# Aux_Lights_Daughter_REV2_1.net
KiCad netlist of a schematic drawn in Altium Designer
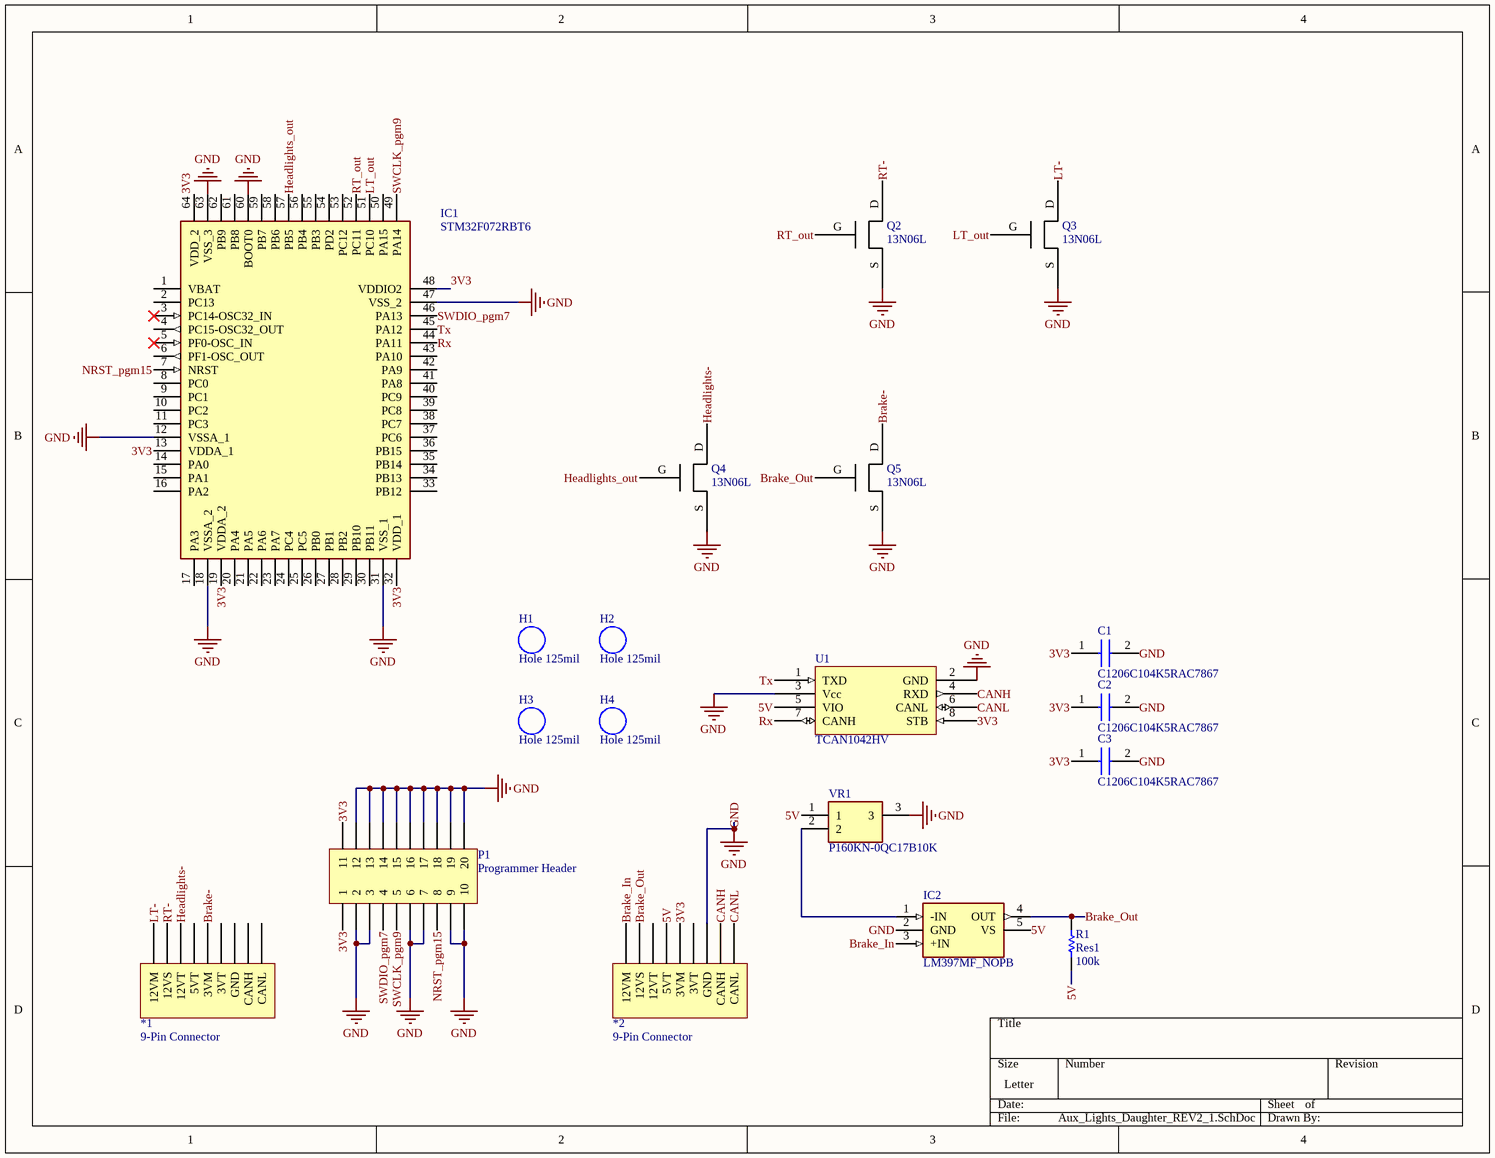
[diagram p0: Aux_Lights_Daughter_REV2_1.SchDoc]

(export (version "E")
  (design (tool "Eeschema 10.0.6"))
  (components
    (comp (ref "*1")
      (value "9-Pin Connector")
      (footprint "9-Pin")
      (libsource (lib "SolarGators") (part "9-Pin Connector"))
    )
    (comp (ref "*2")
      (value "9-Pin Connector")
      (footprint "9-Pin")
      (libsource (lib "SolarGators") (part "9-Pin Connector"))
    )
    (comp (ref "C1")
      (value "C1206C104K5RAC7867")
      (footprint "SamacSys:CAPC3216X110N")
      (description "Capacitor")
      (fields (field (name "MOUSER2 PART NUMBER") "80-C1206104K5RAC7867"))
      (libsource (lib "*") (part "C1206C104K5RAC7867"))
    )
    (comp (ref "C2")
      (value "C1206C104K5RAC7867")
      (footprint "SamacSys:CAPC3216X110N")
      (description "Capacitor")
      (fields (field (name "MOUSER2 PART NUMBER") "80-C1206104K5RAC7867"))
      (libsource (lib "*") (part "C1206C104K5RAC7867"))
    )
    (comp (ref "C3")
      (value "C1206C104K5RAC7867")
      (footprint "SamacSys:CAPC3216X110N")
      (description "Capacitor")
      (fields (field (name "MOUSER2 PART NUMBER") "80-C1206104K5RAC7867"))
      (libsource (lib "*") (part "C1206C104K5RAC7867"))
    )
    (comp (ref "H1")
      (value "Hole 125mil")
      (footprint "Hole 125mil")
      (libsource (lib "ECE LIB new") (part "Hole 125mil"))
    )
    (comp (ref "H2")
      (value "Hole 125mil")
      (footprint "Hole 125mil")
      (libsource (lib "ECE LIB new") (part "Hole 125mil"))
    )
    (comp (ref "H3")
      (value "Hole 125mil")
      (footprint "Hole 125mil")
      (libsource (lib "ECE LIB new") (part "Hole 125mil"))
    )
    (comp (ref "H4")
      (value "Hole 125mil")
      (footprint "Hole 125mil")
      (libsource (lib "ECE LIB new") (part "Hole 125mil"))
    )
    (comp (ref "IC1")
      (value "STM32F072RBT6")
      (footprint "QFP50P1200X1200X160-64N")
      (description "Integrated Circuit")
      (fields (field (name "MOUSER PART NUMBER") "511-STM32F072RBT6"))
      (libsource (lib "solargatorsproject") (part "STM32F072RBT6"))
    )
    (comp (ref "IC2")
      (value "LM397MF_NOPB")
      (footprint "SamacSys:SOT95P280X145-5N")
      (description "Integrated Circuit")
      (fields
        (field (name "MOUSER PART NUMBER") "926-LM397MF/NOPB")
        (field (name "MANUFACTURER_PART_NUMBER") "LM397MF/NOPB")
      )
      (libsource (lib "*") (part "LM397MF_NOPB"))
    )
    (comp (ref "P1")
      (value "Programmer Header")
      (footprint "HDR2X10_CEN")
      (description "Header, 10-Pin, Dual row")
      (fields (field (name "PUBLISHER") "Altium Limited"))
      (libsource (lib "Miscellaneous Connectors") (part "Header 10X2A"))
    )
    (comp (ref "Q2") (value "13N06L") (footprint "13N06L") (libsource (lib "SolarGators") (part "13N06L")))
    (comp (ref "Q3") (value "13N06L") (footprint "13N06L") (libsource (lib "SolarGators") (part "13N06L")))
    (comp (ref "Q4") (value "13N06L") (footprint "13N06L") (libsource (lib "SolarGators") (part "13N06L")))
    (comp (ref "Q5") (value "13N06L") (footprint "13N06L") (libsource (lib "SolarGators") (part "13N06L")))
    (comp (ref "R1")
      (value "Res1")
      (footprint "AXIAL-0.3")
      (description "Resistor")
      (fields (field (name "ALTIUM_VALUE") "100k") (field (name "PUBLISHER") "Altium Limited"))
      (libsource (lib "Miscellaneous Devices") (part "Res1"))
    )
    (comp (ref "U1")
      (value "TCAN1042HV")
      (footprint "CANIC")
      (description "TCAN1042Fault ProtectedCAN Transceiverwith CAN FD")
      (libsource (lib "Schlib1") (part "TCAN1042HV"))
    )
    (comp (ref "VR1")
      (value "P160KN-0QC17B10K")
      (footprint "POT inline wide")
      (description "Variable Resistor")
      (fields (field (name "MOUSER PART NUMBER") "858-P160KN-OQC17B10K"))
      (libsource (lib "*") (part "P160KN-0QC17B10K"))
    )
  )
  (nets
    (net (code "1") (name "/3V3") (class "Default")
      (node (ref "*2") (pin "5") (pinfunction "3VM_5") (pintype "passive"))
      (node (ref "C1") (pin "1") (pinfunction "1_1") (pintype "passive"))
      (node (ref "C2") (pin "1") (pinfunction "1_1") (pintype "passive"))
      (node (ref "C3") (pin "1") (pinfunction "1_1") (pintype "passive"))
      (node (ref "IC1") (pin "13") (pinfunction "VDDA_1_13") (pintype "power_in"))
      (node (ref "IC1") (pin "19") (pinfunction "VDDA_2_19") (pintype "power_in"))
      (node (ref "IC1") (pin "32") (pinfunction "VDD_1_32") (pintype "power_in"))
      (node (ref "IC1") (pin "48") (pinfunction "VDDIO2_48") (pintype "power_in"))
      (node (ref "IC1") (pin "64") (pinfunction "VDD_2_64") (pintype "power_in"))
      (node (ref "P1") (pin "1") (pinfunction "1_1") (pintype "passive"))
      (node (ref "P1") (pin "11") (pinfunction "11_11") (pintype "passive"))
      (node (ref "U1") (pin "8") (pinfunction "STB_8") (pintype "input"))
    )
    (net (code "2") (name "/5V") (class "Default")
      (node (ref "*2") (pin "4") (pinfunction "5VT_4") (pintype "passive"))
      (node (ref "IC2") (pin "5") (pinfunction "VS_5") (pintype "passive"))
      (node (ref "R1") (pin "1") (pinfunction "1_1") (pintype "passive"))
      (node (ref "U1") (pin "5") (pinfunction "VIO_5") (pintype "power_in"))
      (node (ref "VR1") (pin "1") (pinfunction "1_1") (pintype "passive"))
    )
    (net (code "3") (name "/Brake-") (class "Default")
      (node (ref "*1") (pin "5") (pinfunction "3VM_5") (pintype "passive"))
      (node (ref "Q5") (pin "D") (pinfunction "14_D") (pintype "passive"))
    )
    (net (code "4") (name "/Brake_In") (class "Default")
      (node (ref "*2") (pin "1") (pinfunction "12VM_1") (pintype "passive"))
      (node (ref "IC2") (pin "3") (pinfunction "+IN_3") (pintype "input"))
    )
    (net (code "5") (name "/Brake_Out") (class "Default")
      (node (ref "*2") (pin "2") (pinfunction "12VS_2") (pintype "passive"))
      (node (ref "IC2") (pin "4") (pinfunction "OUT_4") (pintype "output"))
      (node (ref "Q5") (pin "G") (pinfunction "13_G") (pintype "passive"))
      (node (ref "R1") (pin "2") (pinfunction "2_2") (pintype "passive"))
    )
    (net (code "6") (name "/CANH") (class "Default")
      (node (ref "*2") (pin "8") (pinfunction "CANH_8") (pintype "passive"))
      (node (ref "U1") (pin "4") (pinfunction "RXD_4") (pintype "output"))
    )
    (net (code "7") (name "/CANL") (class "Default")
      (node (ref "*2") (pin "9") (pinfunction "CANL_9") (pintype "passive"))
      (node (ref "U1") (pin "6") (pinfunction "CANL_6") (pintype "bidirectional"))
    )
    (net (code "8") (name "/Headlights-") (class "Default")
      (node (ref "*1") (pin "3") (pinfunction "12VT_3") (pintype "passive"))
      (node (ref "Q4") (pin "D") (pinfunction "14_D") (pintype "passive"))
    )
    (net (code "9") (name "/Headlights_out") (class "Default")
      (node (ref "IC1") (pin "57") (pinfunction "PB5_57") (pintype "passive"))
      (node (ref "Q4") (pin "G") (pinfunction "13_G") (pintype "passive"))
    )
    (net (code "10") (name "/LT-") (class "Default")
      (node (ref "*1") (pin "1") (pinfunction "12VM_1") (pintype "passive"))
      (node (ref "Q3") (pin "D") (pinfunction "14_D") (pintype "passive"))
    )
    (net (code "11") (name "/LT_out") (class "Default")
      (node (ref "IC1") (pin "51") (pinfunction "PC10_51") (pintype "passive"))
      (node (ref "Q3") (pin "G") (pinfunction "13_G") (pintype "passive"))
    )
    (net (code "12") (name "/NRST_pgm15") (class "Default")
      (node (ref "IC1") (pin "7") (pinfunction "NRST_7") (pintype "input"))
      (node (ref "P1") (pin "8") (pinfunction "8_8") (pintype "passive"))
    )
    (net (code "13") (name "/RT-") (class "Default")
      (node (ref "*1") (pin "2") (pinfunction "12VS_2") (pintype "passive"))
      (node (ref "Q2") (pin "D") (pinfunction "14_D") (pintype "passive"))
    )
    (net (code "14") (name "/RT_out") (class "Default")
      (node (ref "IC1") (pin "52") (pinfunction "PC11_52") (pintype "passive"))
      (node (ref "Q2") (pin "G") (pinfunction "13_G") (pintype "passive"))
    )
    (net (code "15") (name "/Rx") (class "Default")
      (node (ref "IC1") (pin "44") (pinfunction "PA11_44") (pintype "passive"))
      (node (ref "U1") (pin "7") (pinfunction "CANH_7") (pintype "bidirectional"))
    )
    (net (code "16") (name "/SWCLK_pgm9") (class "Default")
      (node (ref "IC1") (pin "49") (pinfunction "PA14_49") (pintype "passive"))
      (node (ref "P1") (pin "5") (pinfunction "5_5") (pintype "passive"))
    )
    (net (code "17") (name "/SWDIO_pgm7") (class "Default")
      (node (ref "IC1") (pin "46") (pinfunction "PA13_46") (pintype "passive"))
      (node (ref "P1") (pin "4") (pinfunction "4_4") (pintype "passive"))
    )
    (net (code "18") (name "/Tx") (class "Default")
      (node (ref "IC1") (pin "45") (pinfunction "PA12_45") (pintype "passive"))
      (node (ref "U1") (pin "1") (pinfunction "TXD_1") (pintype "input"))
    )
    (net (code "19") (name "GND") (class "Default")
      (node (ref "*2") (pin "7") (pinfunction "GND_7") (pintype "passive"))
      (node (ref "C1") (pin "2") (pinfunction "2_2") (pintype "passive"))
      (node (ref "C2") (pin "2") (pinfunction "2_2") (pintype "passive"))
      (node (ref "C3") (pin "2") (pinfunction "2_2") (pintype "passive"))
      (node (ref "IC1") (pin "12") (pinfunction "VSSA_1_12") (pintype "power_in"))
      (node (ref "IC1") (pin "18") (pinfunction "VSSA_2_18") (pintype "power_in"))
      (node (ref "IC1") (pin "31") (pinfunction "VSS_1_31") (pintype "power_in"))
      (node (ref "IC1") (pin "47") (pinfunction "VSS_2_47") (pintype "power_in"))
      (node (ref "IC1") (pin "60") (pinfunction "BOOT0_60") (pintype "passive"))
      (node (ref "IC1") (pin "63") (pinfunction "VSS_3_63") (pintype "power_in"))
      (node (ref "IC2") (pin "2") (pinfunction "GND_2") (pintype "power_in"))
      (node (ref "P1") (pin "10") (pinfunction "10_10") (pintype "passive"))
      (node (ref "P1") (pin "12") (pinfunction "12_12") (pintype "passive"))
      (node (ref "P1") (pin "13") (pinfunction "13_13") (pintype "passive"))
      (node (ref "P1") (pin "14") (pinfunction "14_14") (pintype "passive"))
      (node (ref "P1") (pin "15") (pinfunction "15_15") (pintype "passive"))
      (node (ref "P1") (pin "16") (pinfunction "16_16") (pintype "passive"))
      (node (ref "P1") (pin "17") (pinfunction "17_17") (pintype "passive"))
      (node (ref "P1") (pin "18") (pinfunction "18_18") (pintype "passive"))
      (node (ref "P1") (pin "19") (pinfunction "19_19") (pintype "passive"))
      (node (ref "P1") (pin "2") (pinfunction "2_2") (pintype "passive"))
      (node (ref "P1") (pin "20") (pinfunction "20_20") (pintype "passive"))
      (node (ref "P1") (pin "3") (pinfunction "3_3") (pintype "passive"))
      (node (ref "P1") (pin "6") (pinfunction "6_6") (pintype "passive"))
      (node (ref "P1") (pin "7") (pinfunction "7_7") (pintype "passive"))
      (node (ref "P1") (pin "9") (pinfunction "9_9") (pintype "passive"))
      (node (ref "Q2") (pin "S") (pinfunction "15_S") (pintype "passive"))
      (node (ref "Q3") (pin "S") (pinfunction "15_S") (pintype "passive"))
      (node (ref "Q4") (pin "S") (pinfunction "15_S") (pintype "passive"))
      (node (ref "Q5") (pin "S") (pinfunction "15_S") (pintype "passive"))
      (node (ref "U1") (pin "2") (pinfunction "GND_2") (pintype "power_in"))
      (node (ref "U1") (pin "3") (pinfunction "Vcc_3") (pintype "power_in"))
      (node (ref "VR1") (pin "3") (pinfunction "3_3") (pintype "passive"))
    )
    (net (code "20") (name "Net-(IC2--IN)") (class "Default")
      (node (ref "IC2") (pin "1") (pinfunction "-IN_1") (pintype "input"))
      (node (ref "VR1") (pin "2") (pinfunction "2_2") (pintype "passive"))
    )
    (net (code "21") (name "unconnected-(*1-3VT-Pad6)") (class "Default")
      (node (ref "*1") (pin "6") (pinfunction "3VT_6") (pintype "passive"))
    )
    (net (code "22") (name "unconnected-(*1-5VT-Pad4)") (class "Default")
      (node (ref "*1") (pin "4") (pinfunction "5VT_4") (pintype "passive"))
    )
    (net (code "23") (name "unconnected-(*1-CANH-Pad8)") (class "Default")
      (node (ref "*1") (pin "8") (pinfunction "CANH_8") (pintype "passive"))
    )
    (net (code "24") (name "unconnected-(*1-CANL-Pad9)") (class "Default")
      (node (ref "*1") (pin "9") (pinfunction "CANL_9") (pintype "passive"))
    )
    (net (code "25") (name "unconnected-(*1-GND-Pad7)") (class "Default")
      (node (ref "*1") (pin "7") (pinfunction "GND_7") (pintype "passive"))
    )
    (net (code "26") (name "unconnected-(*2-3VT-Pad6)") (class "Default")
      (node (ref "*2") (pin "6") (pinfunction "3VT_6") (pintype "passive"))
    )
    (net (code "27") (name "unconnected-(*2-12VT-Pad3)") (class "Default")
      (node (ref "*2") (pin "3") (pinfunction "12VT_3") (pintype "passive"))
    )
    (net (code "28") (name "unconnected-(IC1-PA0-Pad14)") (class "Default")
      (node (ref "IC1") (pin "14") (pinfunction "PA0_14") (pintype "passive"))
    )
    (net (code "29") (name "unconnected-(IC1-PA1-Pad15)") (class "Default")
      (node (ref "IC1") (pin "15") (pinfunction "PA1_15") (pintype "passive"))
    )
    (net (code "30") (name "unconnected-(IC1-PA2-Pad16)") (class "Default")
      (node (ref "IC1") (pin "16") (pinfunction "PA2_16") (pintype "passive"))
    )
    (net (code "31") (name "unconnected-(IC1-PA3-Pad17)") (class "Default")
      (node (ref "IC1") (pin "17") (pinfunction "PA3_17") (pintype "passive"))
    )
    (net (code "32") (name "unconnected-(IC1-PA4-Pad20)") (class "Default")
      (node (ref "IC1") (pin "20") (pinfunction "PA4_20") (pintype "passive"))
    )
    (net (code "33") (name "unconnected-(IC1-PA5-Pad21)") (class "Default")
      (node (ref "IC1") (pin "21") (pinfunction "PA5_21") (pintype "passive"))
    )
    (net (code "34") (name "unconnected-(IC1-PA6-Pad22)") (class "Default")
      (node (ref "IC1") (pin "22") (pinfunction "PA6_22") (pintype "passive"))
    )
    (net (code "35") (name "unconnected-(IC1-PA7-Pad23)") (class "Default")
      (node (ref "IC1") (pin "23") (pinfunction "PA7_23") (pintype "passive"))
    )
    (net (code "36") (name "unconnected-(IC1-PA8-Pad41)") (class "Default")
      (node (ref "IC1") (pin "41") (pinfunction "PA8_41") (pintype "passive"))
    )
    (net (code "37") (name "unconnected-(IC1-PA9-Pad42)") (class "Default")
      (node (ref "IC1") (pin "42") (pinfunction "PA9_42") (pintype "passive"))
    )
    (net (code "38") (name "unconnected-(IC1-PA10-Pad43)") (class "Default")
      (node (ref "IC1") (pin "43") (pinfunction "PA10_43") (pintype "passive"))
    )
    (net (code "39") (name "unconnected-(IC1-PA15-Pad50)") (class "Default")
      (node (ref "IC1") (pin "50") (pinfunction "PA15_50") (pintype "passive"))
    )
    (net (code "40") (name "unconnected-(IC1-PB0-Pad26)") (class "Default")
      (node (ref "IC1") (pin "26") (pinfunction "PB0_26") (pintype "passive"))
    )
    (net (code "41") (name "unconnected-(IC1-PB1-Pad27)") (class "Default")
      (node (ref "IC1") (pin "27") (pinfunction "PB1_27") (pintype "passive"))
    )
    (net (code "42") (name "unconnected-(IC1-PB2-Pad28)") (class "Default")
      (node (ref "IC1") (pin "28") (pinfunction "PB2_28") (pintype "passive"))
    )
    (net (code "43") (name "unconnected-(IC1-PB3-Pad55)") (class "Default")
      (node (ref "IC1") (pin "55") (pinfunction "PB3_55") (pintype "passive"))
    )
    (net (code "44") (name "unconnected-(IC1-PB4-Pad56)") (class "Default")
      (node (ref "IC1") (pin "56") (pinfunction "PB4_56") (pintype "passive"))
    )
    (net (code "45") (name "unconnected-(IC1-PB6-Pad58)") (class "Default")
      (node (ref "IC1") (pin "58") (pinfunction "PB6_58") (pintype "passive"))
    )
    (net (code "46") (name "unconnected-(IC1-PB7-Pad59)") (class "Default")
      (node (ref "IC1") (pin "59") (pinfunction "PB7_59") (pintype "passive"))
    )
    (net (code "47") (name "unconnected-(IC1-PB8-Pad61)") (class "Default")
      (node (ref "IC1") (pin "61") (pinfunction "PB8_61") (pintype "passive"))
    )
    (net (code "48") (name "unconnected-(IC1-PB9-Pad62)") (class "Default")
      (node (ref "IC1") (pin "62") (pinfunction "PB9_62") (pintype "passive"))
    )
    (net (code "49") (name "unconnected-(IC1-PB10-Pad29)") (class "Default")
      (node (ref "IC1") (pin "29") (pinfunction "PB10_29") (pintype "passive"))
    )
    (net (code "50") (name "unconnected-(IC1-PB11-Pad30)") (class "Default")
      (node (ref "IC1") (pin "30") (pinfunction "PB11_30") (pintype "passive"))
    )
    (net (code "51") (name "unconnected-(IC1-PB12-Pad33)") (class "Default")
      (node (ref "IC1") (pin "33") (pinfunction "PB12_33") (pintype "passive"))
    )
    (net (code "52") (name "unconnected-(IC1-PB13-Pad34)") (class "Default")
      (node (ref "IC1") (pin "34") (pinfunction "PB13_34") (pintype "passive"))
    )
    (net (code "53") (name "unconnected-(IC1-PB14-Pad35)") (class "Default")
      (node (ref "IC1") (pin "35") (pinfunction "PB14_35") (pintype "passive"))
    )
    (net (code "54") (name "unconnected-(IC1-PB15-Pad36)") (class "Default")
      (node (ref "IC1") (pin "36") (pinfunction "PB15_36") (pintype "passive"))
    )
    (net (code "55") (name "unconnected-(IC1-PC0-Pad8)") (class "Default")
      (node (ref "IC1") (pin "8") (pinfunction "PC0_8") (pintype "passive"))
    )
    (net (code "56") (name "unconnected-(IC1-PC1-Pad9)") (class "Default")
      (node (ref "IC1") (pin "9") (pinfunction "PC1_9") (pintype "passive"))
    )
    (net (code "57") (name "unconnected-(IC1-PC2-Pad10)") (class "Default")
      (node (ref "IC1") (pin "10") (pinfunction "PC2_10") (pintype "passive"))
    )
    (net (code "58") (name "unconnected-(IC1-PC3-Pad11)") (class "Default")
      (node (ref "IC1") (pin "11") (pinfunction "PC3_11") (pintype "passive"))
    )
    (net (code "59") (name "unconnected-(IC1-PC4-Pad24)") (class "Default")
      (node (ref "IC1") (pin "24") (pinfunction "PC4_24") (pintype "passive"))
    )
    (net (code "60") (name "unconnected-(IC1-PC5-Pad25)") (class "Default")
      (node (ref "IC1") (pin "25") (pinfunction "PC5_25") (pintype "passive"))
    )
    (net (code "61") (name "unconnected-(IC1-PC6-Pad37)") (class "Default")
      (node (ref "IC1") (pin "37") (pinfunction "PC6_37") (pintype "passive"))
    )
    (net (code "62") (name "unconnected-(IC1-PC7-Pad38)") (class "Default")
      (node (ref "IC1") (pin "38") (pinfunction "PC7_38") (pintype "passive"))
    )
    (net (code "63") (name "unconnected-(IC1-PC8-Pad39)") (class "Default")
      (node (ref "IC1") (pin "39") (pinfunction "PC8_39") (pintype "passive"))
    )
    (net (code "64") (name "unconnected-(IC1-PC9-Pad40)") (class "Default")
      (node (ref "IC1") (pin "40") (pinfunction "PC9_40") (pintype "passive"))
    )
    (net (code "65") (name "unconnected-(IC1-PC12-Pad53)") (class "Default")
      (node (ref "IC1") (pin "53") (pinfunction "PC12_53") (pintype "passive"))
    )
    (net (code "66") (name "unconnected-(IC1-PC13-Pad2)") (class "Default")
      (node (ref "IC1") (pin "2") (pinfunction "PC13_2") (pintype "passive"))
    )
    (net (code "67") (name "unconnected-(IC1-PC14-OSC32_IN-Pad3)") (class "Default")
      (node (ref "IC1") (pin "3") (pinfunction "PC14-OSC32_IN_3") (pintype "input+no_connect"))
    )
    (net (code "68") (name "unconnected-(IC1-PC15-OSC32_OUT-Pad4)") (class "Default")
      (node (ref "IC1") (pin "4") (pinfunction "PC15-OSC32_OUT_4") (pintype "output"))
    )
    (net (code "69") (name "unconnected-(IC1-PD2-Pad54)") (class "Default")
      (node (ref "IC1") (pin "54") (pinfunction "PD2_54") (pintype "passive"))
    )
    (net (code "70") (name "unconnected-(IC1-PF0-OSC_IN-Pad5)") (class "Default")
      (node (ref "IC1") (pin "5") (pinfunction "PF0-OSC_IN_5") (pintype "input+no_connect"))
    )
    (net (code "71") (name "unconnected-(IC1-PF1-OSC_OUT-Pad6)") (class "Default")
      (node (ref "IC1") (pin "6") (pinfunction "PF1-OSC_OUT_6") (pintype "output"))
    )
    (net (code "72") (name "unconnected-(IC1-VBAT-Pad1)") (class "Default")
      (node (ref "IC1") (pin "1") (pinfunction "VBAT_1") (pintype "passive"))
    )
  )
)
